# 468323_001_Laser_Interface.net
KiCad netlist of a schematic drawn in Altium Designer
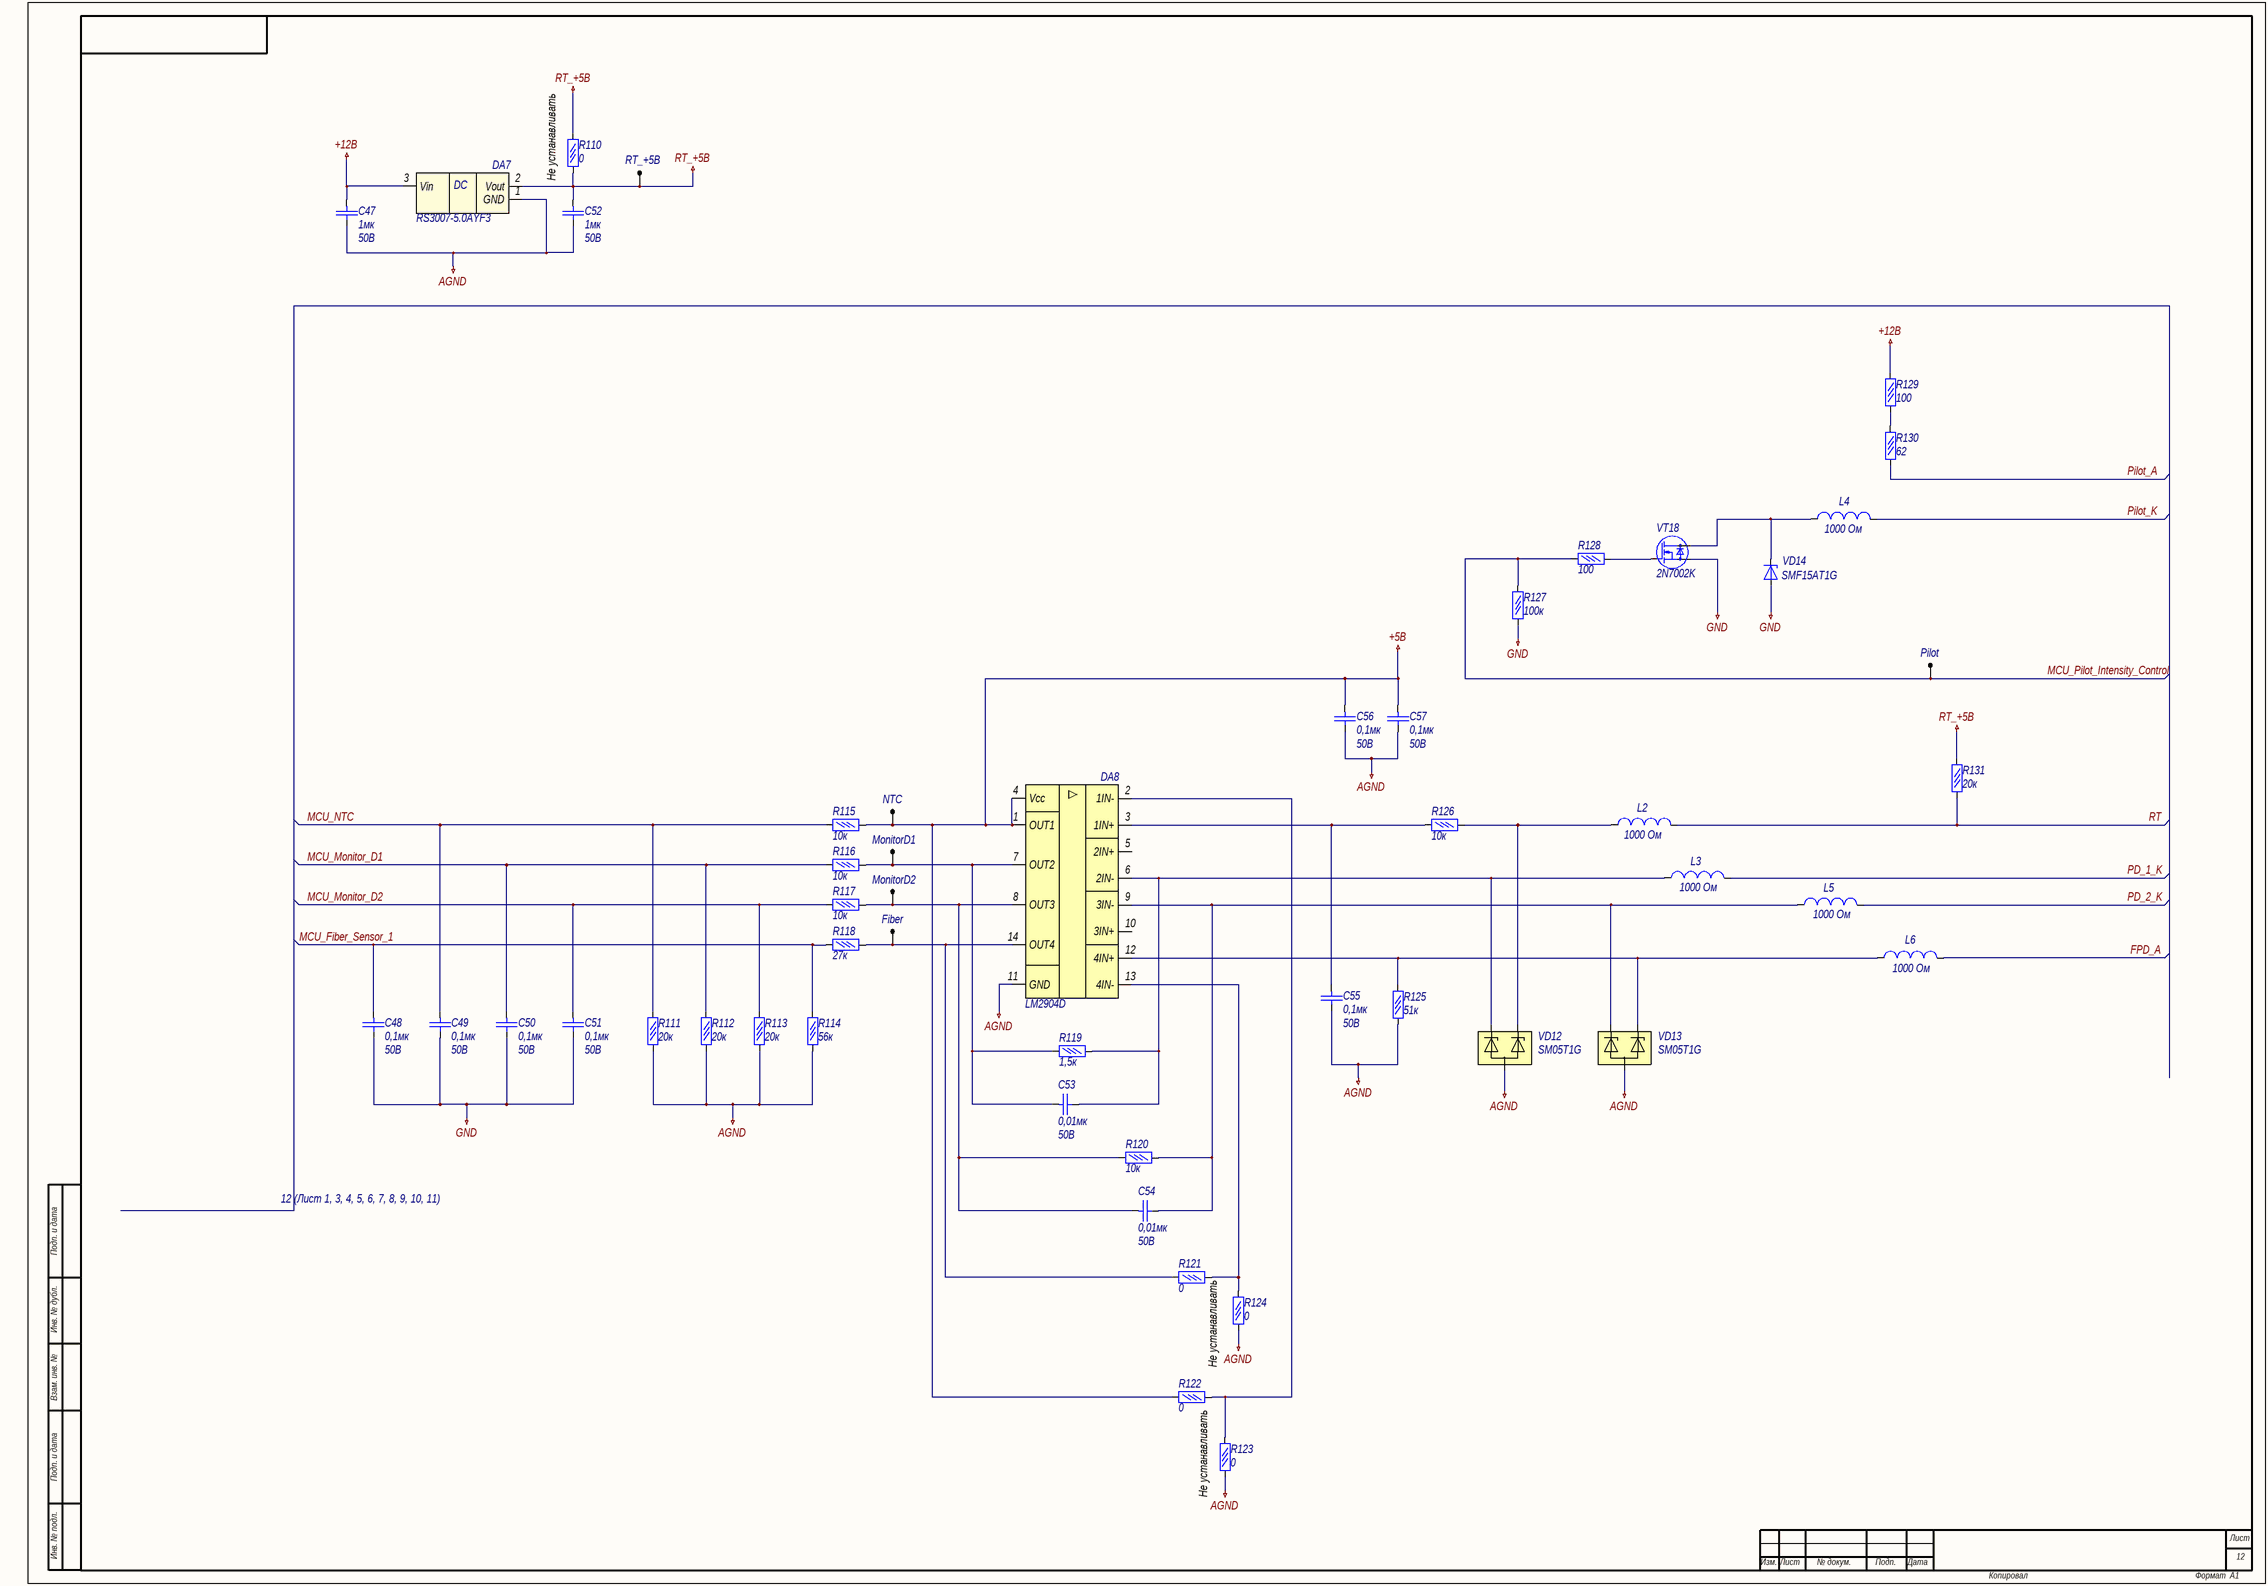
[diagram p0: РЕУН.468323.001_Laser_Interface.SchDoc]

(export (version "E")
  (design (tool "Eeschema 10.0.6"))
  (components
    (comp (ref "C47")
      (value "1мк")
      (footprint "C0805_AA")
      (description "Конденсатор кер.")
      (fields (field (name "VOLTAGE") "50В"))
      (libsource (lib "Library_Diana") (part "Конденсатор кер."))
    )
    (comp (ref "C48")
      (value "0,1мк")
      (footprint "C0805_AA")
      (description "Конденсатор кер.")
      (fields (field (name "VOLTAGE") "50В"))
      (libsource (lib "Library_Diana") (part "Конденсатор кер."))
    )
    (comp (ref "C49")
      (value "0,1мк")
      (footprint "C0805_AA")
      (description "Конденсатор кер.")
      (fields (field (name "VOLTAGE") "50В"))
      (libsource (lib "Library_Diana") (part "Конденсатор кер."))
    )
    (comp (ref "C50")
      (value "0,1мк")
      (footprint "C0805_AA")
      (description "Конденсатор кер.")
      (fields (field (name "VOLTAGE") "50В"))
      (libsource (lib "Library_Diana") (part "Конденсатор кер."))
    )
    (comp (ref "C51")
      (value "0,1мк")
      (footprint "C0805_AA")
      (description "Конденсатор кер.")
      (fields (field (name "VOLTAGE") "50В"))
      (libsource (lib "Library_Diana") (part "Конденсатор кер."))
    )
    (comp (ref "C52")
      (value "1мк")
      (footprint "C0805_AA")
      (description "Конденсатор кер.")
      (fields (field (name "VOLTAGE") "50В"))
      (libsource (lib "Library_Diana") (part "Конденсатор кер."))
    )
    (comp (ref "C53")
      (value "0,01мк")
      (footprint "C0805_AA")
      (description "Конденсатор кер.")
      (fields (field (name "VOLTAGE") "50В"))
      (libsource (lib "Library_Diana") (part "Конденсатор кер."))
    )
    (comp (ref "C54")
      (value "0,01мк")
      (footprint "C0805_AA")
      (description "Конденсатор кер.")
      (fields (field (name "VOLTAGE") "50В"))
      (libsource (lib "Library_Diana") (part "Конденсатор кер."))
    )
    (comp (ref "C55")
      (value "0,1мк")
      (footprint "C0805_AA")
      (description "Конденсатор кер.")
      (fields (field (name "VOLTAGE") "50В"))
      (libsource (lib "Library_Diana") (part "Конденсатор кер."))
    )
    (comp (ref "C56")
      (value "0,1мк")
      (footprint "C0805_AA")
      (description "Конденсатор кер.")
      (fields (field (name "VOLTAGE") "50В"))
      (libsource (lib "Library_Diana") (part "Конденсатор кер."))
    )
    (comp (ref "C57")
      (value "0,1мк")
      (footprint "C0805_AA")
      (description "Конденсатор кер.")
      (fields (field (name "VOLTAGE") "50В"))
      (libsource (lib "Library_Diana") (part "Конденсатор кер."))
    )
    (comp (ref "DA7")
      (value "RS3007-5.0AYF3")
      (description "Линейный стабилизатор напряжения")
      (libsource (lib "Library_Diana") (part "L78_1"))
    )
    (comp (ref "DA8")
      (value "LM2904D")
      (footprint "SO8_H")
      (description "ОУ")
      (fields (field (name "NAME") "LM2904D"))
      (libsource (lib "Library_Diana") (part "LM2902D"))
    )
    (comp (ref "Fiber")
      (value "\"1\"")
      (footprint "0.5 x 1_round")
      (description "Test point")
      (libsource (lib "TarabusLib_KOR") (part "TestPoint"))
    )
    (comp (ref "L2")
      (value "1000 Ом")
      (footprint "L0603_A")
      (description "Катушка индуктивности")
      (libsource (lib "Library_Diana") (part "Inductor"))
    )
    (comp (ref "L3")
      (value "1000 Ом")
      (footprint "L0603_A")
      (description "Катушка индуктивности")
      (libsource (lib "Library_Diana") (part "Inductor"))
    )
    (comp (ref "L4")
      (value "1000 Ом")
      (footprint "L0603_A")
      (description "Катушка индуктивности")
      (libsource (lib "Library_Diana") (part "Inductor"))
    )
    (comp (ref "L5")
      (value "1000 Ом")
      (footprint "L0603_A")
      (description "Катушка индуктивности")
      (libsource (lib "Library_Diana") (part "Inductor"))
    )
    (comp (ref "L6")
      (value "1000 Ом")
      (footprint "L0603_A")
      (description "Катушка индуктивности")
      (libsource (lib "Library_Diana") (part "Inductor"))
    )
    (comp (ref "MonitorD1")
      (value "\"1\"")
      (footprint "0.5 x 1_round")
      (description "Test point")
      (libsource (lib "TarabusLib_KOR") (part "TestPoint"))
    )
    (comp (ref "MonitorD2")
      (value "\"1\"")
      (footprint "0.5 x 1_round")
      (description "Test point")
      (libsource (lib "TarabusLib_KOR") (part "TestPoint"))
    )
    (comp (ref "NTC")
      (value "\"1\"")
      (footprint "0.5 x 1_round")
      (description "Test point")
      (libsource (lib "TarabusLib_KOR") (part "TestPoint"))
    )
    (comp (ref "Pilot")
      (value "\"1\"")
      (footprint "0.5 x 1_round")
      (description "Test point")
      (libsource (lib "TarabusLib_KOR") (part "TestPoint"))
    )
    (comp (ref "R110")
      (value "0")
      (footprint "R1206")
      (description "Резистор 0,05Вт")
      (libsource (lib "") (part "Резистор  0,05Вт_3"))
    )
    (comp (ref "R111")
      (value "20к")
      (footprint "R1206")
      (description "Резистор 0,05Вт")
      (libsource (lib "") (part "Резистор  0,05Вт_1"))
    )
    (comp (ref "R112")
      (value "20к")
      (footprint "R1206")
      (description "Резистор 0,05Вт")
      (libsource (lib "") (part "Резистор  0,05Вт_1"))
    )
    (comp (ref "R113")
      (value "20к")
      (footprint "R1206")
      (description "Резистор 0,05Вт")
      (libsource (lib "") (part "Резистор  0,05Вт_1"))
    )
    (comp (ref "R114")
      (value "56к")
      (footprint "R1206")
      (description "Резистор 0,05Вт")
      (libsource (lib "") (part "Резистор  0,05Вт_1"))
    )
    (comp (ref "R115")
      (value "10к")
      (footprint "R1206")
      (description "Резистор 0,05Вт")
      (libsource (lib "Library_Diana") (part "Резистор  0,05Вт"))
    )
    (comp (ref "R116")
      (value "10к")
      (footprint "R1206")
      (description "Резистор 0,05Вт")
      (libsource (lib "Library_Diana") (part "Резистор  0,05Вт"))
    )
    (comp (ref "R117")
      (value "10к")
      (footprint "R1206")
      (description "Резистор 0,05Вт")
      (libsource (lib "Library_Diana") (part "Резистор  0,05Вт"))
    )
    (comp (ref "R118")
      (value "27к")
      (footprint "R1206")
      (description "Резистор 0,05Вт")
      (libsource (lib "Library_Diana") (part "Резистор  0,05Вт"))
    )
    (comp (ref "R119")
      (value "1,5к")
      (footprint "R1206")
      (description "Резистор 0,05Вт")
      (libsource (lib "Library_Diana") (part "Резистор  0,05Вт"))
    )
    (comp (ref "R120")
      (value "10к")
      (footprint "R1206")
      (description "Резистор 0,05Вт")
      (libsource (lib "Library_Diana") (part "Резистор  0,05Вт"))
    )
    (comp (ref "R121")
      (value "0")
      (footprint "R1206")
      (description "Резистор 0,05Вт")
      (libsource (lib "") (part "Резистор  0,05Вт_2"))
    )
    (comp (ref "R122")
      (value "0")
      (footprint "R1206")
      (description "Резистор 0,05Вт")
      (libsource (lib "") (part "Резистор  0,05Вт_2"))
    )
    (comp (ref "R123")
      (value "0")
      (footprint "R1206")
      (description "Резистор 0,05Вт")
      (libsource (lib "") (part "Резистор  0,05Вт_3"))
    )
    (comp (ref "R124")
      (value "0")
      (footprint "R1206")
      (description "Резистор 0,05Вт")
      (libsource (lib "") (part "Резистор  0,05Вт_3"))
    )
    (comp (ref "R125")
      (value "51к")
      (footprint "R1206")
      (description "Резистор 0,05Вт")
      (libsource (lib "") (part "Резистор  0,05Вт_3"))
    )
    (comp (ref "R126")
      (value "10к")
      (footprint "R1206")
      (description "Резистор 0,05Вт")
      (libsource (lib "Library_Diana") (part "Резистор  0,05Вт"))
    )
    (comp (ref "R127")
      (value "100к")
      (footprint "R1206")
      (description "Резистор 0,05Вт")
      (libsource (lib "") (part "Резистор  0,05Вт_1"))
    )
    (comp (ref "R128")
      (value "100")
      (footprint "R1206")
      (description "Резистор 0,05Вт")
      (libsource (lib "Library_Diana") (part "Резистор  0,05Вт"))
    )
    (comp (ref "R129")
      (value "100")
      (footprint "R1206")
      (description "Резистор 0,05Вт")
      (libsource (lib "") (part "Резистор  0,05Вт_1"))
    )
    (comp (ref "R130")
      (value "62")
      (footprint "R1206")
      (description "Резистор 0,05Вт")
      (libsource (lib "") (part "Резистор  0,05Вт_1"))
    )
    (comp (ref "R131")
      (value "20к")
      (footprint "R1206")
      (description "Резистор 0,05Вт")
      (libsource (lib "") (part "Резистор  0,05Вт_1"))
    )
    (comp (ref "RT_+5В")
      (value "\"1\"")
      (footprint "0.5 x 1_round")
      (description "Test point")
      (libsource (lib "TarabusLib_KOR") (part "TestPoint"))
    )
    (comp (ref "VD12")
      (value "SM05T1G")
      (description "Сборка TVS-диодов")
      (libsource (lib "Library_Diana") (part "ZenerArray2"))
    )
    (comp (ref "VD13")
      (value "SM05T1G")
      (description "Сборка TVS-диодов")
      (libsource (lib "Library_Diana") (part "ZenerArray2"))
    )
    (comp (ref "VD14")
      (value "SMF15AT1G")
      (footprint "SOT23-2_A")
      (description "Стабилитрон")
      (libsource (lib "Library_Diana") (part "DiodeZener"))
    )
    (comp (ref "VT18")
      (value "2N7002K")
      (footprint "SOT:SOT23-3")
      (fields (field (name "NAME") "2N7002K"))
      (libsource (lib "Library_Diana") (part "mosfet-n"))
    )
  )
  (nets
    (net (code "1") (name "+5В") (class "Default")
      (node (ref "C56") (pin "2") (pinfunction "2_2") (pintype "passive"))
      (node (ref "C57") (pin "2") (pinfunction "2_2") (pintype "passive"))
      (node (ref "DA8") (pin "1") (pinfunction "OUT1_1") (pintype "passive"))
      (node (ref "DA8") (pin "4") (pinfunction "Vcc_4") (pintype "passive"))
      (node (ref "NTC") (pin "1") (pinfunction "1_1") (pintype "passive"))
      (node (ref "R115") (pin "2") (pinfunction "2_2") (pintype "passive"))
      (node (ref "R122") (pin "2") (pinfunction "2_2") (pintype "passive"))
    )
    (net (code "2") (name "+12В") (class "Default")
      (node (ref "C47") (pin "2") (pinfunction "2_2") (pintype "passive"))
      (node (ref "DA7") (pin "3") (pinfunction "Vin_3") (pintype "power_in"))
      (node (ref "R129") (pin "2") (pinfunction "2_2") (pintype "passive"))
    )
    (net (code "3") (name "/FPD_A") (class "Default")
      (node (ref "L6") (pin "2") (pinfunction "2_2") (pintype "passive"))
    )
    (net (code "4") (name "/MCU_Fiber_Sensor_1") (class "Default")
      (node (ref "C48") (pin "2") (pinfunction "2_2") (pintype "passive"))
      (node (ref "R114") (pin "2") (pinfunction "2_2") (pintype "passive"))
      (node (ref "R118") (pin "1") (pinfunction "1_1") (pintype "passive"))
    )
    (net (code "5") (name "/MCU_Monitor_D1") (class "Default")
      (node (ref "C50") (pin "2") (pinfunction "2_2") (pintype "passive"))
      (node (ref "R112") (pin "2") (pinfunction "2_2") (pintype "passive"))
      (node (ref "R116") (pin "1") (pinfunction "1_1") (pintype "passive"))
    )
    (net (code "6") (name "/MCU_Monitor_D2") (class "Default")
      (node (ref "C51") (pin "2") (pinfunction "2_2") (pintype "passive"))
      (node (ref "R113") (pin "2") (pinfunction "2_2") (pintype "passive"))
      (node (ref "R117") (pin "1") (pinfunction "1_1") (pintype "passive"))
    )
    (net (code "7") (name "/MCU_NTC") (class "Default")
      (node (ref "C49") (pin "2") (pinfunction "2_2") (pintype "passive"))
      (node (ref "R111") (pin "2") (pinfunction "2_2") (pintype "passive"))
      (node (ref "R115") (pin "1") (pinfunction "1_1") (pintype "passive"))
    )
    (net (code "8") (name "/MCU_Pilot_Intensity_Control") (class "Default")
      (node (ref "Pilot") (pin "1") (pinfunction "1_1") (pintype "passive"))
      (node (ref "R127") (pin "2") (pinfunction "2_2") (pintype "passive"))
      (node (ref "R128") (pin "1") (pinfunction "1_1") (pintype "passive"))
    )
    (net (code "9") (name "/PD_1_K") (class "Default")
      (node (ref "L3") (pin "2") (pinfunction "2_2") (pintype "passive"))
    )
    (net (code "10") (name "/PD_2_K") (class "Default")
      (node (ref "L5") (pin "2") (pinfunction "2_2") (pintype "passive"))
    )
    (net (code "11") (name "/Pilot_A") (class "Default")
      (node (ref "R130") (pin "1") (pinfunction "1_1") (pintype "passive"))
    )
    (net (code "12") (name "/Pilot_K") (class "Default")
      (node (ref "L4") (pin "2") (pinfunction "2_2") (pintype "passive"))
    )
    (net (code "13") (name "/RT") (class "Default")
      (node (ref "L2") (pin "2") (pinfunction "2_2") (pintype "passive"))
      (node (ref "R131") (pin "1") (pinfunction "1_1") (pintype "passive"))
    )
    (net (code "14") (name "AGND") (class "Default")
      (node (ref "C47") (pin "1") (pinfunction "1_1") (pintype "passive"))
      (node (ref "C52") (pin "1") (pinfunction "1_1") (pintype "passive"))
      (node (ref "C55") (pin "1") (pinfunction "1_1") (pintype "passive"))
      (node (ref "C56") (pin "1") (pinfunction "1_1") (pintype "passive"))
      (node (ref "C57") (pin "1") (pinfunction "1_1") (pintype "passive"))
      (node (ref "DA7") (pin "1") (pinfunction "GND_1") (pintype "power_in"))
      (node (ref "DA8") (pin "11") (pinfunction "GND_11") (pintype "passive"))
      (node (ref "R111") (pin "1") (pinfunction "1_1") (pintype "passive"))
      (node (ref "R112") (pin "1") (pinfunction "1_1") (pintype "passive"))
      (node (ref "R113") (pin "1") (pinfunction "1_1") (pintype "passive"))
      (node (ref "R114") (pin "1") (pinfunction "1_1") (pintype "passive"))
      (node (ref "R123") (pin "2") (pinfunction "2_2") (pintype "passive"))
      (node (ref "R124") (pin "2") (pinfunction "2_2") (pintype "passive"))
      (node (ref "R125") (pin "2") (pinfunction "2_2") (pintype "passive"))
      (node (ref "VD12") (pin "3") (pintype "passive"))
      (node (ref "VD13") (pin "3") (pintype "passive"))
    )
    (net (code "15") (name "GND") (class "Default")
      (node (ref "C48") (pin "1") (pinfunction "1_1") (pintype "passive"))
      (node (ref "C49") (pin "1") (pinfunction "1_1") (pintype "passive"))
      (node (ref "C50") (pin "1") (pinfunction "1_1") (pintype "passive"))
      (node (ref "C51") (pin "1") (pinfunction "1_1") (pintype "passive"))
      (node (ref "R127") (pin "1") (pinfunction "1_1") (pintype "passive"))
      (node (ref "VD14") (pin "2") (pinfunction "A_2") (pintype "passive"))
      (node (ref "VT18") (pin "2") (pinfunction "S_2") (pintype "passive"))
    )
    (net (code "16") (name "Net-(DA8-1IN+)") (class "Default")
      (node (ref "C55") (pin "2") (pinfunction "2_2") (pintype "passive"))
      (node (ref "DA8") (pin "3") (pinfunction "1IN+_3") (pintype "passive"))
      (node (ref "R126") (pin "1") (pinfunction "1_1") (pintype "passive"))
    )
    (net (code "17") (name "Net-(DA8-1IN-)") (class "Default")
      (node (ref "DA8") (pin "2") (pinfunction "1IN-_2") (pintype "passive"))
      (node (ref "R122") (pin "1") (pinfunction "1_1") (pintype "passive"))
      (node (ref "R123") (pin "1") (pinfunction "1_1") (pintype "passive"))
    )
    (net (code "18") (name "Net-(DA8-2IN-)") (class "Default")
      (node (ref "C53") (pin "1") (pinfunction "1_1") (pintype "passive"))
      (node (ref "DA8") (pin "6") (pinfunction "2IN-_6") (pintype "passive"))
      (node (ref "L3") (pin "1") (pinfunction "1_1") (pintype "passive"))
      (node (ref "R119") (pin "2") (pinfunction "2_2") (pintype "passive"))
      (node (ref "VD12") (pin "1") (pintype "passive"))
    )
    (net (code "19") (name "Net-(DA8-3IN-)") (class "Default")
      (node (ref "C54") (pin "1") (pinfunction "1_1") (pintype "passive"))
      (node (ref "DA8") (pin "9") (pinfunction "3IN-_9") (pintype "passive"))
      (node (ref "L5") (pin "1") (pinfunction "1_1") (pintype "passive"))
      (node (ref "R120") (pin "2") (pinfunction "2_2") (pintype "passive"))
      (node (ref "VD13") (pin "1") (pintype "passive"))
    )
    (net (code "20") (name "Net-(DA8-4IN+)") (class "Default")
      (node (ref "DA8") (pin "12") (pinfunction "4IN+_12") (pintype "passive"))
      (node (ref "L6") (pin "1") (pinfunction "1_1") (pintype "passive"))
      (node (ref "R125") (pin "1") (pinfunction "1_1") (pintype "passive"))
      (node (ref "VD13") (pin "2") (pintype "passive"))
    )
    (net (code "21") (name "Net-(DA8-4IN-)") (class "Default")
      (node (ref "DA8") (pin "13") (pinfunction "4IN-_13") (pintype "passive"))
      (node (ref "R121") (pin "1") (pinfunction "1_1") (pintype "passive"))
      (node (ref "R124") (pin "1") (pinfunction "1_1") (pintype "passive"))
    )
    (net (code "22") (name "Net-(DA8-OUT2)") (class "Default")
      (node (ref "C53") (pin "2") (pinfunction "2_2") (pintype "passive"))
      (node (ref "DA8") (pin "7") (pinfunction "OUT2_7") (pintype "passive"))
      (node (ref "MonitorD1") (pin "1") (pinfunction "1_1") (pintype "passive"))
      (node (ref "R116") (pin "2") (pinfunction "2_2") (pintype "passive"))
      (node (ref "R119") (pin "1") (pinfunction "1_1") (pintype "passive"))
    )
    (net (code "23") (name "Net-(DA8-OUT3)") (class "Default")
      (node (ref "C54") (pin "2") (pinfunction "2_2") (pintype "passive"))
      (node (ref "DA8") (pin "8") (pinfunction "OUT3_8") (pintype "passive"))
      (node (ref "MonitorD2") (pin "1") (pinfunction "1_1") (pintype "passive"))
      (node (ref "R117") (pin "2") (pinfunction "2_2") (pintype "passive"))
      (node (ref "R120") (pin "1") (pinfunction "1_1") (pintype "passive"))
    )
    (net (code "24") (name "Net-(DA8-OUT4)") (class "Default")
      (node (ref "DA8") (pin "14") (pinfunction "OUT4_14") (pintype "passive"))
      (node (ref "Fiber") (pin "1") (pinfunction "1_1") (pintype "passive"))
      (node (ref "R118") (pin "2") (pinfunction "2_2") (pintype "passive"))
      (node (ref "R121") (pin "2") (pinfunction "2_2") (pintype "passive"))
    )
    (net (code "25") (name "Net-(L2-Pad1)") (class "Default")
      (node (ref "L2") (pin "1") (pinfunction "1_1") (pintype "passive"))
      (node (ref "R126") (pin "2") (pinfunction "2_2") (pintype "passive"))
      (node (ref "VD12") (pin "2") (pintype "passive"))
    )
    (net (code "26") (name "Net-(R129-Pad1)") (class "Default")
      (node (ref "R129") (pin "1") (pinfunction "1_1") (pintype "passive"))
      (node (ref "R130") (pin "2") (pinfunction "2_2") (pintype "passive"))
    )
    (net (code "27") (name "Net-(VD14-K)") (class "Default")
      (node (ref "L4") (pin "1") (pinfunction "1_1") (pintype "passive"))
      (node (ref "VD14") (pin "1") (pinfunction "K_1") (pintype "passive"))
      (node (ref "VT18") (pin "3") (pinfunction "D_3") (pintype "passive"))
    )
    (net (code "28") (name "Net-(VT18-G)") (class "Default")
      (node (ref "R128") (pin "2") (pinfunction "2_2") (pintype "passive"))
      (node (ref "VT18") (pin "1") (pinfunction "G_1") (pintype "passive"))
    )
    (net (code "29") (name "RT_+5В") (class "Default")
      (node (ref "C52") (pin "2") (pinfunction "2_2") (pintype "passive"))
      (node (ref "DA7") (pin "2") (pinfunction "Vout_2") (pintype "power_in"))
      (node (ref "R110") (pin "1") (pinfunction "1_1") (pintype "passive"))
      (node (ref "R110") (pin "2") (pinfunction "2_2") (pintype "passive"))
      (node (ref "R131") (pin "2") (pinfunction "2_2") (pintype "passive"))
      (node (ref "RT_+5В") (pin "1") (pinfunction "1_1") (pintype "passive"))
    )
    (net (code "30") (name "unconnected-(DA8-2IN+-Pad5)") (class "Default")
      (node (ref "DA8") (pin "5") (pinfunction "2IN+_5") (pintype "passive"))
    )
    (net (code "31") (name "unconnected-(DA8-3IN+-Pad10)") (class "Default")
      (node (ref "DA8") (pin "10") (pinfunction "3IN+_10") (pintype "passive"))
    )
  )
)
